# Sheet1.net
KiCad netlist of a schematic drawn in Altium Designer
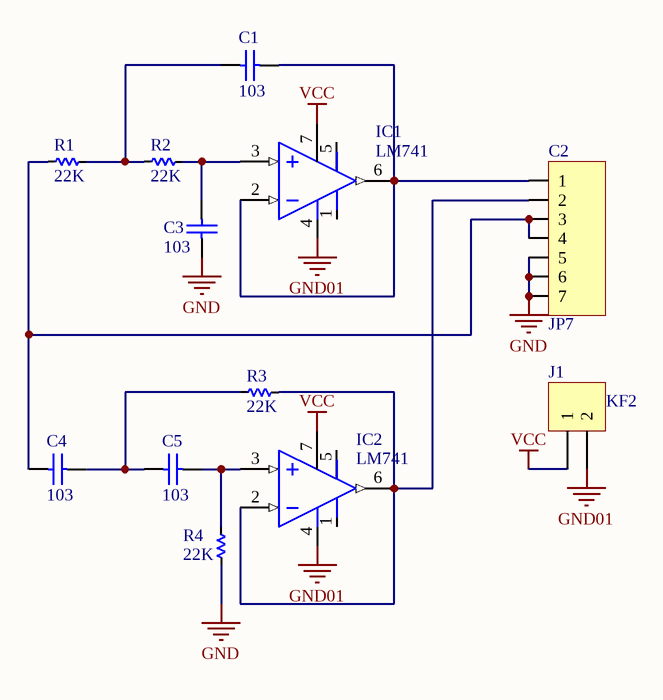
[diagram p0: Sheet1.SchDoc]

(export (version "E")
  (design (tool "Eeschema 10.0.6"))
  (components
    (comp (ref "C1")
      (value "103")
      (footprint "Cap Non-Pol 3mm")
      (description "Non-polarized Capacitor")
      (fields (field (name "Comment") "Cap Non-pol") (field (name "PUBLISHER") "Altium Limited"))
      (libsource (lib "hphonglib") (part "Cap Non-pol"))
    )
    (comp (ref "C2")
      (value "JP7")
      (footprint "JP7-D1T")
      (description "WR-PHD 2.54 mm Angled Socket Header")
      (fields
        (field (name "MANUFACTURER") "Würth Elektronik eiSos GmbH")
        (field (name "PARTNO") "613007143121")
        (field (name "CREATED BY") "Karrer Zheng")
      )
      (libsource (lib "LIBRARY") (part "JP7"))
    )
    (comp (ref "C3")
      (value "103")
      (footprint "Cap Non-Pol 3mm")
      (description "Non-polarized Capacitor")
      (fields (field (name "Comment") "Cap Non-pol") (field (name "PUBLISHER") "Altium Limited"))
      (libsource (lib "hphonglib") (part "Cap Non-pol"))
    )
    (comp (ref "C4")
      (value "103")
      (footprint "Cap Non-Pol 3mm")
      (description "Non-polarized Capacitor")
      (fields (field (name "Comment") "Cap Non-pol") (field (name "PUBLISHER") "Altium Limited"))
      (libsource (lib "hphonglib") (part "Cap Non-pol"))
    )
    (comp (ref "C5")
      (value "103")
      (footprint "Cap Non-Pol 3mm")
      (description "Non-polarized Capacitor")
      (fields (field (name "Comment") "Cap Non-pol") (field (name "PUBLISHER") "Altium Limited"))
      (libsource (lib "hphonglib") (part "Cap Non-pol"))
    )
    (comp (ref "IC1")
      (value "LM741")
      (footprint "DIP8")
      (description "Single OA")
      (libsource (lib "LIBRARY") (part "LM741"))
    )
    (comp (ref "IC2")
      (value "LM741")
      (footprint "DIP8")
      (description "Single OA")
      (libsource (lib "LIBRARY") (part "LM741"))
    )
    (comp (ref "J1")
      (value "KF2")
      (footprint "KF2-3.5")
      (fields
        (field (name "MANUFACTURER") "Würth Elektronik eiSos GmbH")
        (field (name "PARTNO") "691103110002")
        (field (name "CREATED BY") "Karrer Zheng")
      )
      (libsource (lib "LIBRARY") (part "KF2"))
    )
    (comp (ref "R1")
      (value "22K")
      (footprint "RES-1/4W")
      (description "Res")
      (fields
        (field (name "MANUFACTURER") "Generic Components")
        (field (name "PUBLISHER") "Altium Hobart Technology Centre")
      )
      (libsource (lib "LIBRARY") (part "Res"))
    )
    (comp (ref "R2")
      (value "22K")
      (footprint "RES-1/4W")
      (description "Res")
      (fields
        (field (name "MANUFACTURER") "Generic Components")
        (field (name "PUBLISHER") "Altium Hobart Technology Centre")
      )
      (libsource (lib "LIBRARY") (part "Res"))
    )
    (comp (ref "R3")
      (value "22K")
      (footprint "RES-1/4W")
      (description "Res")
      (fields
        (field (name "MANUFACTURER") "Generic Components")
        (field (name "PUBLISHER") "Altium Hobart Technology Centre")
      )
      (libsource (lib "LIBRARY") (part "Res"))
    )
    (comp (ref "R4")
      (value "22K")
      (footprint "RES-1/4W")
      (description "Res")
      (fields
        (field (name "MANUFACTURER") "Generic Components")
        (field (name "PUBLISHER") "Altium Hobart Technology Centre")
      )
      (libsource (lib "LIBRARY") (part "Res"))
    )
  )
  (nets
    (net (code "1") (name "GND") (class "Default")
      (node (ref "C2") (pin "5") (pinfunction "5_5") (pintype "passive"))
      (node (ref "C2") (pin "6") (pinfunction "6_6") (pintype "passive"))
      (node (ref "C2") (pin "7") (pinfunction "7_7") (pintype "passive"))
      (node (ref "C3") (pin "1") (pinfunction "1_1") (pintype "passive"))
      (node (ref "R4") (pin "2") (pinfunction "2_2") (pintype "passive"))
    )
    (net (code "2") (name "GND01") (class "Default")
      (node (ref "IC1") (pin "4") (pinfunction "-V_4") (pintype "passive"))
      (node (ref "IC2") (pin "4") (pinfunction "-V_4") (pintype "passive"))
      (node (ref "J1") (pin "2") (pinfunction "2_2") (pintype "passive"))
    )
    (net (code "3") (name "Net-(C1-Pad1)") (class "Default")
      (node (ref "C1") (pin "1") (pinfunction "1_1") (pintype "passive"))
      (node (ref "R1") (pin "1") (pinfunction "1_1") (pintype "passive"))
      (node (ref "R2") (pin "2") (pinfunction "2_2") (pintype "passive"))
    )
    (net (code "4") (name "Net-(C2-Pad3)") (class "Default")
      (node (ref "C2") (pin "3") (pinfunction "3_3") (pintype "passive"))
      (node (ref "C2") (pin "4") (pinfunction "4_4") (pintype "passive"))
      (node (ref "C4") (pin "1") (pinfunction "1_1") (pintype "passive"))
      (node (ref "R1") (pin "2") (pinfunction "2_2") (pintype "passive"))
    )
    (net (code "5") (name "Net-(C4-Pad2)") (class "Default")
      (node (ref "C4") (pin "2") (pinfunction "2_2") (pintype "passive"))
      (node (ref "C5") (pin "1") (pinfunction "1_1") (pintype "passive"))
      (node (ref "R3") (pin "2") (pinfunction "2_2") (pintype "passive"))
    )
    (net (code "6") (name "Net-(IC1-IN+)") (class "Default")
      (node (ref "C3") (pin "2") (pinfunction "2_2") (pintype "passive"))
      (node (ref "IC1") (pin "3") (pinfunction "IN+_3") (pintype "input"))
      (node (ref "R2") (pin "1") (pinfunction "1_1") (pintype "passive"))
    )
    (net (code "7") (name "Net-(IC1-IN-)") (class "Default")
      (node (ref "C1") (pin "2") (pinfunction "2_2") (pintype "passive"))
      (node (ref "C2") (pin "1") (pinfunction "1_1") (pintype "passive"))
      (node (ref "IC1") (pin "2") (pinfunction "IN-_2") (pintype "input"))
      (node (ref "IC1") (pin "6") (pinfunction "OUT_6") (pintype "output"))
    )
    (net (code "8") (name "Net-(IC2-IN+)") (class "Default")
      (node (ref "C5") (pin "2") (pinfunction "2_2") (pintype "passive"))
      (node (ref "IC2") (pin "3") (pinfunction "IN+_3") (pintype "input"))
      (node (ref "R4") (pin "1") (pinfunction "1_1") (pintype "passive"))
    )
    (net (code "9") (name "Net-(IC2-IN-)") (class "Default")
      (node (ref "C2") (pin "2") (pinfunction "2_2") (pintype "passive"))
      (node (ref "IC2") (pin "2") (pinfunction "IN-_2") (pintype "input"))
      (node (ref "IC2") (pin "6") (pinfunction "OUT_6") (pintype "output"))
      (node (ref "R3") (pin "1") (pinfunction "1_1") (pintype "passive"))
    )
    (net (code "10") (name "VCC") (class "Default")
      (node (ref "IC1") (pin "7") (pinfunction "+V_7") (pintype "passive"))
      (node (ref "IC2") (pin "7") (pinfunction "+V_7") (pintype "passive"))
      (node (ref "J1") (pin "1") (pinfunction "1_1") (pintype "passive"))
    )
    (net (code "11") (name "unconnected-(IC1-Vos-Pad1)") (class "Default")
      (node (ref "IC1") (pin "1") (pinfunction "Vos_1") (pintype "passive"))
    )
    (net (code "12") (name "unconnected-(IC1-Vos-Pad5)") (class "Default")
      (node (ref "IC1") (pin "5") (pinfunction "Vos_5") (pintype "passive"))
    )
    (net (code "13") (name "unconnected-(IC2-Vos-Pad1)") (class "Default")
      (node (ref "IC2") (pin "1") (pinfunction "Vos_1") (pintype "passive"))
    )
    (net (code "14") (name "unconnected-(IC2-Vos-Pad5)") (class "Default")
      (node (ref "IC2") (pin "5") (pinfunction "Vos_5") (pintype "passive"))
    )
  )
)
